# ASCII_08_FPGA_banks_1_2_3_4.net
KiCad netlist of a schematic drawn in Altium Designer
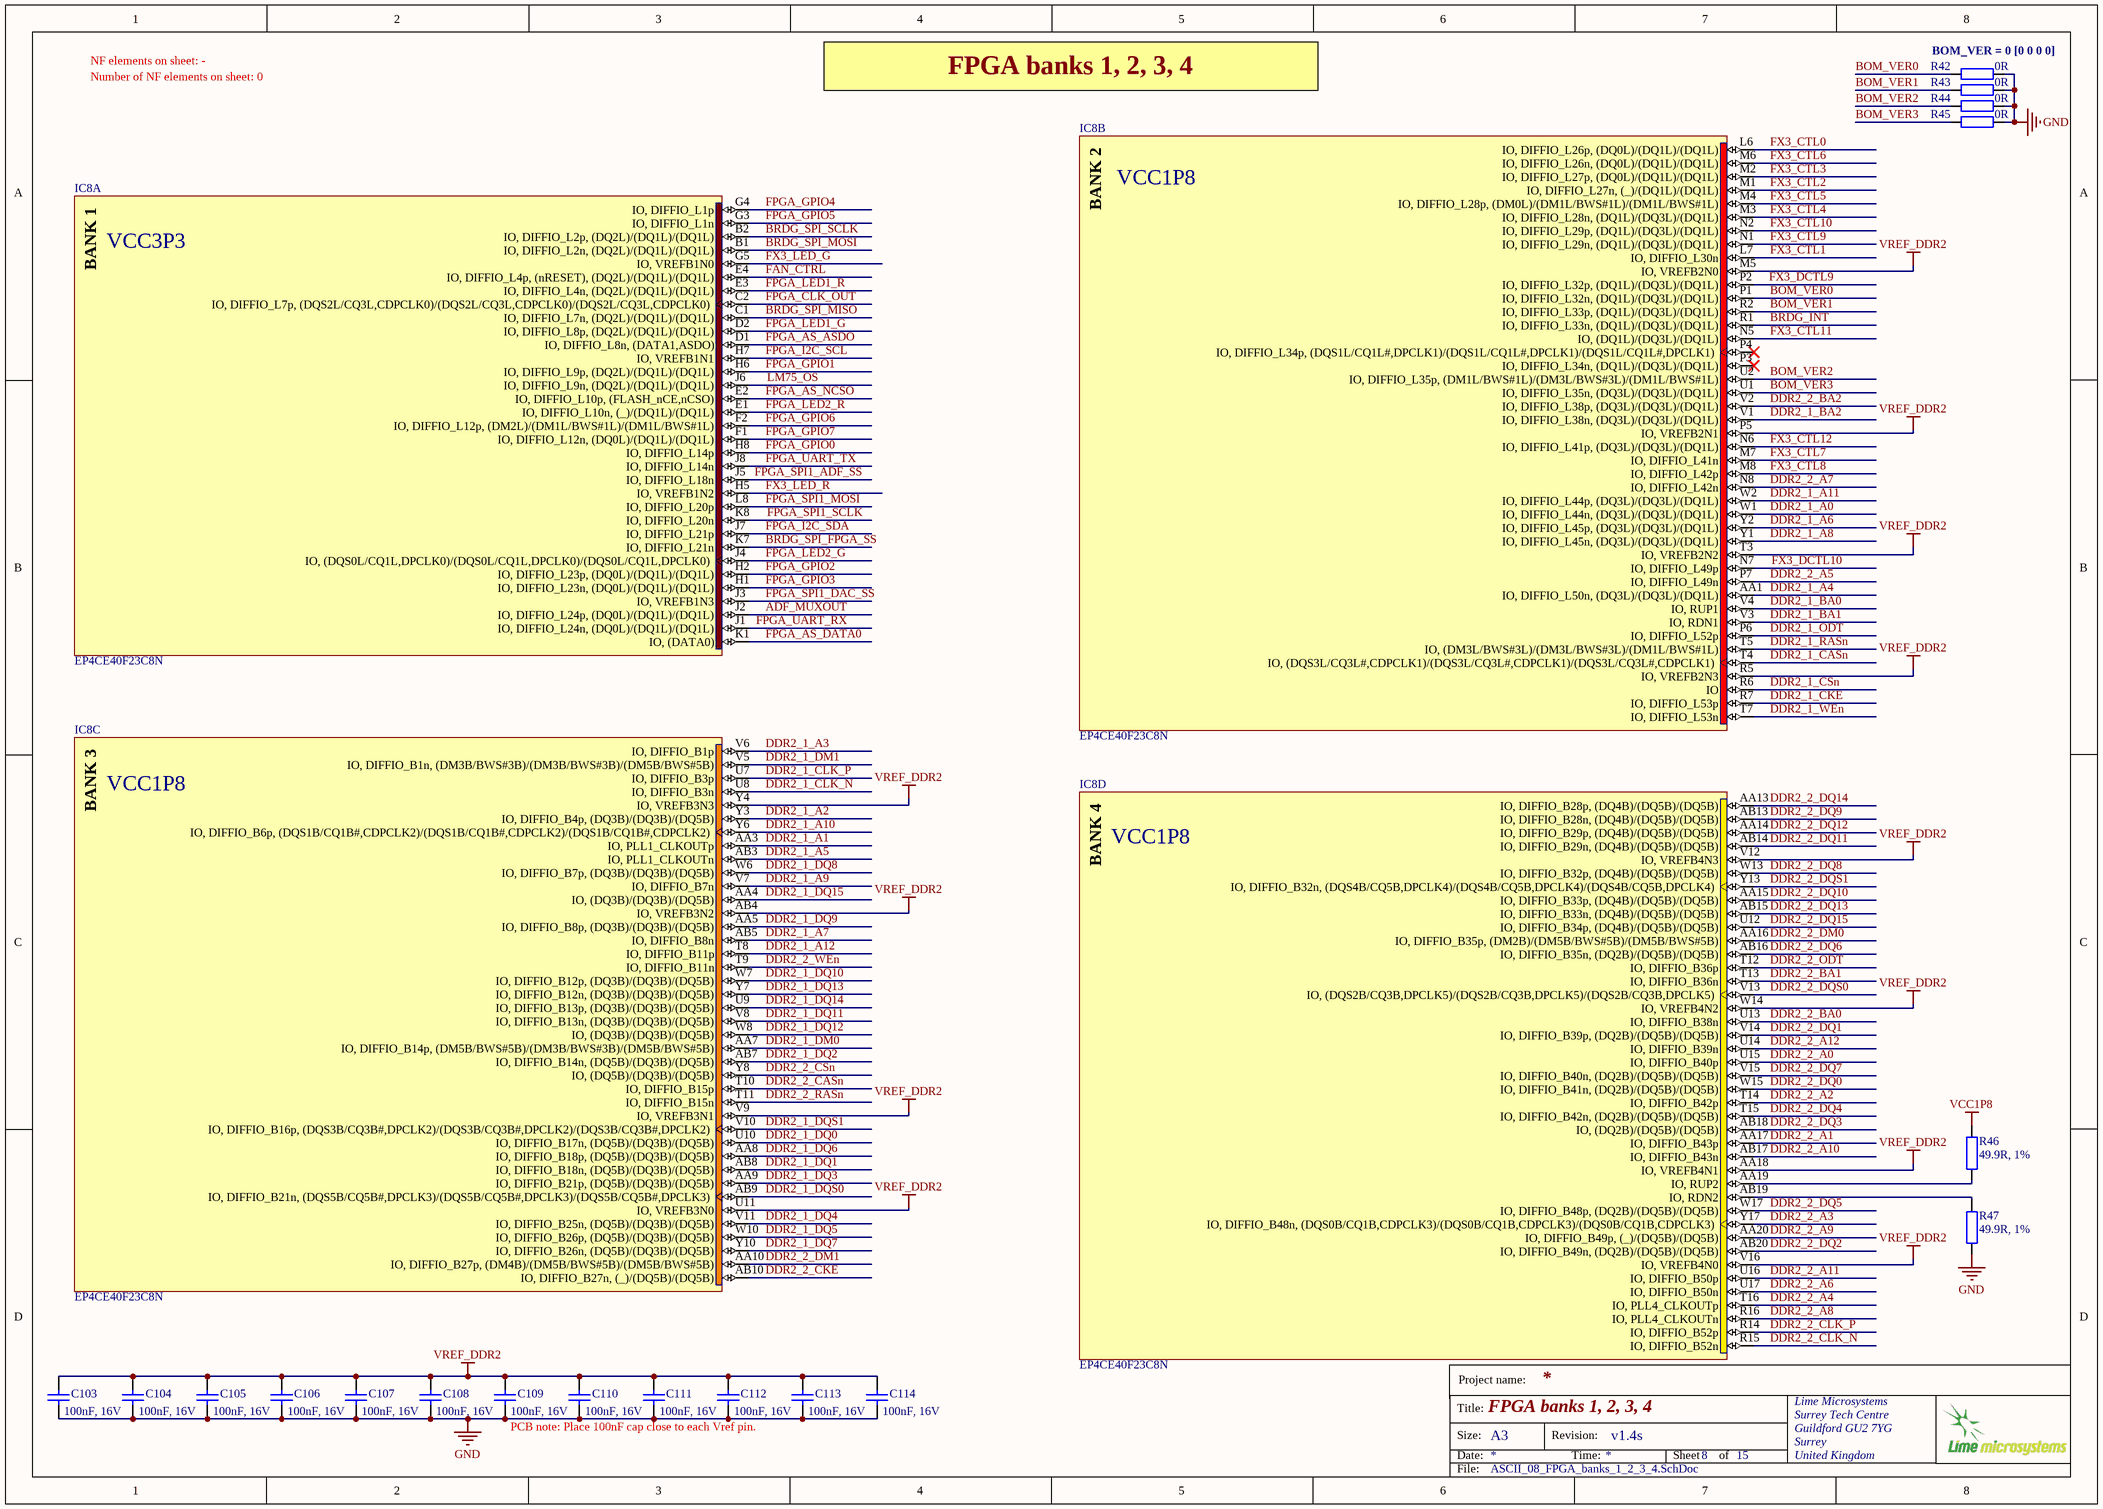
[diagram p0: ASCII_08_FPGA_banks_1_2_3_4.SchDoc]

(export (version "E")
  (design (tool "Eeschema 10.0.6"))
  (components
    (comp (ref "C103")
      (value "100nF, 16V")
      (footprint "CAP0402")
      (fields
        (field (name "TOLERANCE") "10 %")
        (field (name "MANUFACTURER") "Murata Electronics")
        (field (name "MANUFACTURER PART NUMBER") "GRM155R71C104KA88D")
      )
      (libsource (lib "LimeFPGAboard_schLib") (part "Cap_0603"))
    )
    (comp (ref "C104")
      (value "100nF, 16V")
      (footprint "CAP0402")
      (fields
        (field (name "TOLERANCE") "10 %")
        (field (name "MANUFACTURER") "Murata Electronics")
        (field (name "MANUFACTURER PART NUMBER") "GRM155R71C104KA88D")
      )
      (libsource (lib "LimeFPGAboard_schLib") (part "Cap_0603"))
    )
    (comp (ref "C105")
      (value "100nF, 16V")
      (footprint "CAP0402")
      (fields
        (field (name "TOLERANCE") "10 %")
        (field (name "MANUFACTURER") "Murata Electronics")
        (field (name "MANUFACTURER PART NUMBER") "GRM155R71C104KA88D")
      )
      (libsource (lib "LimeFPGAboard_schLib") (part "Cap_0603"))
    )
    (comp (ref "C106")
      (value "100nF, 16V")
      (footprint "CAP0402")
      (fields
        (field (name "TOLERANCE") "10 %")
        (field (name "MANUFACTURER") "Murata Electronics")
        (field (name "MANUFACTURER PART NUMBER") "GRM155R71C104KA88D")
      )
      (libsource (lib "LimeFPGAboard_schLib") (part "Cap_0603"))
    )
    (comp (ref "C107")
      (value "100nF, 16V")
      (footprint "CAP0402")
      (fields
        (field (name "TOLERANCE") "10 %")
        (field (name "MANUFACTURER") "Murata Electronics")
        (field (name "MANUFACTURER PART NUMBER") "GRM155R71C104KA88D")
      )
      (libsource (lib "LimeFPGAboard_schLib") (part "Cap_0603"))
    )
    (comp (ref "C108")
      (value "100nF, 16V")
      (footprint "CAP0402")
      (fields
        (field (name "TOLERANCE") "10 %")
        (field (name "MANUFACTURER") "Murata Electronics")
        (field (name "MANUFACTURER PART NUMBER") "GRM155R71C104KA88D")
      )
      (libsource (lib "LimeFPGAboard_schLib") (part "Cap_0603"))
    )
    (comp (ref "C109")
      (value "100nF, 16V")
      (footprint "CAP0402")
      (fields
        (field (name "TOLERANCE") "10 %")
        (field (name "MANUFACTURER") "Murata Electronics")
        (field (name "MANUFACTURER PART NUMBER") "GRM155R71C104KA88D")
      )
      (libsource (lib "LimeFPGAboard_schLib") (part "Cap_0603"))
    )
    (comp (ref "C110")
      (value "100nF, 16V")
      (footprint "CAP0402")
      (fields
        (field (name "TOLERANCE") "10 %")
        (field (name "MANUFACTURER") "Murata Electronics")
        (field (name "MANUFACTURER PART NUMBER") "GRM155R71C104KA88D")
      )
      (libsource (lib "LimeFPGAboard_schLib") (part "Cap_0603"))
    )
    (comp (ref "C111")
      (value "100nF, 16V")
      (footprint "CAP0402")
      (fields
        (field (name "TOLERANCE") "10 %")
        (field (name "MANUFACTURER") "Murata Electronics")
        (field (name "MANUFACTURER PART NUMBER") "GRM155R71C104KA88D")
      )
      (libsource (lib "LimeFPGAboard_schLib") (part "Cap_0603"))
    )
    (comp (ref "C112")
      (value "100nF, 16V")
      (footprint "CAP0402")
      (fields
        (field (name "TOLERANCE") "10 %")
        (field (name "MANUFACTURER") "Murata Electronics")
        (field (name "MANUFACTURER PART NUMBER") "GRM155R71C104KA88D")
      )
      (libsource (lib "LimeFPGAboard_schLib") (part "Cap_0603"))
    )
    (comp (ref "C113")
      (value "100nF, 16V")
      (footprint "CAP0402")
      (fields
        (field (name "TOLERANCE") "10 %")
        (field (name "MANUFACTURER") "Murata Electronics")
        (field (name "MANUFACTURER PART NUMBER") "GRM155R71C104KA88D")
      )
      (libsource (lib "LimeFPGAboard_schLib") (part "Cap_0603"))
    )
    (comp (ref "C114")
      (value "100nF, 16V")
      (footprint "CAP0402")
      (fields
        (field (name "TOLERANCE") "10 %")
        (field (name "MANUFACTURER") "Murata Electronics")
        (field (name "MANUFACTURER PART NUMBER") "GRM155R71C104KA88D")
      )
      (libsource (lib "LimeFPGAboard_schLib") (part "Cap_0603"))
    )
    (comp (ref "IC8")
      (value "EP4CE40F23C8N")
      (footprint "FBGA484_A-240")
      (description "IC FPGA 328 I/O 484FBGA")
      (fields (field (name "MANUFACTURER") "Altera"))
      (libsource (lib "LimeMicroAltiumLib_schLib") (part "EP4CE40F23C7N"))
    )
    (comp (ref "R42")
      (value "0R")
      (footprint "RES0402")
      (fields (field (name "MANUFACTURER") "Yageo"))
      (libsource (lib "LimeFPGAboard_schLib") (part "Res_0402"))
    )
    (comp (ref "R43")
      (value "0R")
      (footprint "RES0402")
      (fields (field (name "MANUFACTURER") "Yageo"))
      (libsource (lib "LimeFPGAboard_schLib") (part "Res_0402"))
    )
    (comp (ref "R44")
      (value "0R")
      (footprint "RES0402")
      (fields (field (name "MANUFACTURER") "Yageo"))
      (libsource (lib "LimeFPGAboard_schLib") (part "Res_0402"))
    )
    (comp (ref "R45")
      (value "0R")
      (footprint "RES0402")
      (fields (field (name "MANUFACTURER") "Yageo"))
      (libsource (lib "LimeFPGAboard_schLib") (part "Res_0402"))
    )
    (comp (ref "R46")
      (value "49.9R, 1%")
      (footprint "RES0402")
      (fields
        (field (name "TOLERANCE") "±1%")
        (field (name "MANUFACTURER") "Samsung Electro-Mechanics America, Inc.")
        (field (name "MANUFACTURER PART NUMBER") "RC1005F49R9CS")
      )
      (libsource (lib "LimeMicroAltiumLib_schLib") (part "Res_0402"))
    )
    (comp (ref "R47")
      (value "49.9R, 1%")
      (footprint "RES0402")
      (fields
        (field (name "TOLERANCE") "±1%")
        (field (name "MANUFACTURER") "Samsung Electro-Mechanics America, Inc.")
        (field (name "MANUFACTURER PART NUMBER") "RC1005F49R9CS")
      )
      (libsource (lib "LimeMicroAltiumLib_schLib") (part "Res_0402"))
    )
  )
  (nets
    (net (code "1") (name "/ADF_MUXOUT") (class "Default")
      (node (ref "IC8") (pin "J2") (pinfunction "IO,_DIFFIO_L24p,_(DQ0L)/(DQ1L)/(DQ1L)_J2") (pintype "bidirectional"))
    )
    (net (code "2") (name "/BOM_VER0") (class "Default")
      (node (ref "IC8") (pin "P1") (pinfunction "IO,_DIFFIO_L32n,_(DQ1L)/(DQ3L)/(DQ1L)_P1") (pintype "bidirectional"))
      (node (ref "R42") (pin "1") (pinfunction "1_1") (pintype "passive"))
    )
    (net (code "3") (name "/BOM_VER1") (class "Default")
      (node (ref "IC8") (pin "R2") (pinfunction "IO,_DIFFIO_L33p,_(DQ1L)/(DQ3L)/(DQ1L)_R2") (pintype "bidirectional"))
      (node (ref "R43") (pin "1") (pinfunction "1_1") (pintype "passive"))
    )
    (net (code "4") (name "/BOM_VER2") (class "Default")
      (node (ref "IC8") (pin "U2") (pinfunction "IO,_DIFFIO_L35p,_(DM1L/BWS#1L)/(DM3L/BWS#3L)/(DM1L/BWS#1L)_U2") (pintype "bidirectional"))
      (node (ref "R44") (pin "1") (pinfunction "1_1") (pintype "passive"))
    )
    (net (code "5") (name "/BOM_VER3") (class "Default")
      (node (ref "IC8") (pin "U1") (pinfunction "IO,_DIFFIO_L35n,_(DQ3L)/(DQ3L)/(DQ1L)_U1") (pintype "bidirectional"))
      (node (ref "R45") (pin "1") (pinfunction "1_1") (pintype "passive"))
    )
    (net (code "6") (name "/BRDG_INT") (class "Default")
      (node (ref "IC8") (pin "R1") (pinfunction "IO,_DIFFIO_L33n,_(DQ1L)/(DQ3L)/(DQ1L)_R1") (pintype "bidirectional"))
    )
    (net (code "7") (name "/BRDG_SPI_FPGA_SS") (class "Default")
      (node (ref "IC8") (pin "K7") (pinfunction "IO,_DIFFIO_L21n_K7") (pintype "bidirectional"))
    )
    (net (code "8") (name "/BRDG_SPI_MISO") (class "Default")
      (node (ref "IC8") (pin "C1") (pinfunction "IO,_DIFFIO_L7n,_(DQ2L)/(DQ1L)/(DQ1L)_C1") (pintype "bidirectional"))
    )
    (net (code "9") (name "/BRDG_SPI_MOSI") (class "Default")
      (node (ref "IC8") (pin "B1") (pinfunction "IO,_DIFFIO_L2n,_(DQ2L)/(DQ1L)/(DQ1L)_B1") (pintype "bidirectional"))
    )
    (net (code "10") (name "/BRDG_SPI_SCLK") (class "Default")
      (node (ref "IC8") (pin "B2") (pinfunction "IO,_DIFFIO_L2p,_(DQ2L)/(DQ1L)/(DQ1L)_B2") (pintype "bidirectional"))
    )
    (net (code "11") (name "/DDR2_1_A0") (class "Default")
      (node (ref "IC8") (pin "W1") (pinfunction "IO,_DIFFIO_L44n,_(DQ3L)/(DQ3L)/(DQ1L)_W1") (pintype "bidirectional"))
    )
    (net (code "12") (name "/DDR2_1_A1") (class "Default")
      (node (ref "IC8") (pin "AA3") (pinfunction "IO,_PLL1_CLKOUTp_AA3") (pintype "bidirectional"))
    )
    (net (code "13") (name "/DDR2_1_A2") (class "Default")
      (node (ref "IC8") (pin "Y3") (pinfunction "IO,_DIFFIO_B4p,_(DQ3B)/(DQ3B)/(DQ5B)_Y3") (pintype "bidirectional"))
    )
    (net (code "14") (name "/DDR2_1_A3") (class "Default")
      (node (ref "IC8") (pin "V6") (pinfunction "IO,_DIFFIO_B1p_V6") (pintype "bidirectional"))
    )
    (net (code "15") (name "/DDR2_1_A4") (class "Default")
      (node (ref "IC8") (pin "AA1") (pinfunction "IO,_DIFFIO_L50n,_(DQ3L)/(DQ3L)/(DQ1L)_AA1") (pintype "bidirectional"))
    )
    (net (code "16") (name "/DDR2_1_A5") (class "Default")
      (node (ref "IC8") (pin "AB3") (pinfunction "IO,_PLL1_CLKOUTn_AB3") (pintype "bidirectional"))
    )
    (net (code "17") (name "/DDR2_1_A6") (class "Default")
      (node (ref "IC8") (pin "Y2") (pinfunction "IO,_DIFFIO_L45p,_(DQ3L)/(DQ3L)/(DQ1L)_Y2") (pintype "bidirectional"))
    )
    (net (code "18") (name "/DDR2_1_A7") (class "Default")
      (node (ref "IC8") (pin "AB5") (pinfunction "IO,_DIFFIO_B8n_AB5") (pintype "bidirectional"))
    )
    (net (code "19") (name "/DDR2_1_A8") (class "Default")
      (node (ref "IC8") (pin "Y1") (pinfunction "IO,_DIFFIO_L45n,_(DQ3L)/(DQ3L)/(DQ1L)_Y1") (pintype "bidirectional"))
    )
    (net (code "20") (name "/DDR2_1_A9") (class "Default")
      (node (ref "IC8") (pin "V7") (pinfunction "IO,_DIFFIO_B7n_V7") (pintype "bidirectional"))
    )
    (net (code "21") (name "/DDR2_1_A10") (class "Default")
      (node (ref "IC8") (pin "Y6") (pinfunction "IO,_DIFFIO_B6p,_(DQS1B/CQ1B#,CDPCLK2)/(DQS1B/CQ1B#,CDPCLK2)/(DQS1B/CQ1B#,CDPCLK2)_Y6") (pintype "bidirectional"))
    )
    (net (code "22") (name "/DDR2_1_A11") (class "Default")
      (node (ref "IC8") (pin "W2") (pinfunction "IO,_DIFFIO_L44p,_(DQ3L)/(DQ3L)/(DQ1L)_W2") (pintype "bidirectional"))
    )
    (net (code "23") (name "/DDR2_1_A12") (class "Default")
      (node (ref "IC8") (pin "T8") (pinfunction "IO,_DIFFIO_B11p_T8") (pintype "bidirectional"))
    )
    (net (code "24") (name "/DDR2_1_BA0") (class "Default")
      (node (ref "IC8") (pin "V4") (pinfunction "IO,_RUP1_V4") (pintype "bidirectional"))
    )
    (net (code "25") (name "/DDR2_1_BA1") (class "Default")
      (node (ref "IC8") (pin "V3") (pinfunction "IO,_RDN1_V3") (pintype "bidirectional"))
    )
    (net (code "26") (name "/DDR2_1_BA2") (class "Default")
      (node (ref "IC8") (pin "V1") (pinfunction "IO,_DIFFIO_L38n,_(DQ3L)/(DQ3L)/(DQ1L)_V1") (pintype "bidirectional"))
    )
    (net (code "27") (name "/DDR2_1_CASn") (class "Default")
      (node (ref "IC8") (pin "T4") (pinfunction "IO,_(DQS3L/CQ3L#,CDPCLK1)/(DQS3L/CQ3L#,CDPCLK1)/(DQS3L/CQ3L#,CDPCLK1)_T4") (pintype "bidirectional"))
    )
    (net (code "28") (name "/DDR2_1_CKE") (class "Default")
      (node (ref "IC8") (pin "R7") (pinfunction "IO,_DIFFIO_L53p_R7") (pintype "bidirectional"))
    )
    (net (code "29") (name "/DDR2_1_CLK_N") (class "Default")
      (node (ref "IC8") (pin "U8") (pinfunction "IO,_DIFFIO_B3n_U8") (pintype "bidirectional"))
    )
    (net (code "30") (name "/DDR2_1_CLK_P") (class "Default")
      (node (ref "IC8") (pin "U7") (pinfunction "IO,_DIFFIO_B3p_U7") (pintype "bidirectional"))
    )
    (net (code "31") (name "/DDR2_1_CSn") (class "Default")
      (node (ref "IC8") (pin "R6") (pinfunction "IO_R6") (pintype "bidirectional"))
    )
    (net (code "32") (name "/DDR2_1_DM0") (class "Default")
      (node (ref "IC8") (pin "AA7") (pinfunction "IO,_DIFFIO_B14p,_(DM5B/BWS#5B)/(DM3B/BWS#3B)/(DM5B/BWS#5B)_AA7") (pintype "bidirectional"))
    )
    (net (code "33") (name "/DDR2_1_DM1") (class "Default")
      (node (ref "IC8") (pin "V5") (pinfunction "IO,_DIFFIO_B1n,_(DM3B/BWS#3B)/(DM3B/BWS#3B)/(DM5B/BWS#5B)_V5") (pintype "bidirectional"))
    )
    (net (code "34") (name "/DDR2_1_DQ0") (class "Default")
      (node (ref "IC8") (pin "U10") (pinfunction "IO,_DIFFIO_B17n,_(DQ5B)/(DQ3B)/(DQ5B)_U10") (pintype "bidirectional"))
    )
    (net (code "35") (name "/DDR2_1_DQ1") (class "Default")
      (node (ref "IC8") (pin "AB8") (pinfunction "IO,_DIFFIO_B18n,_(DQ5B)/(DQ3B)/(DQ5B)_AB8") (pintype "bidirectional"))
    )
    (net (code "36") (name "/DDR2_1_DQ2") (class "Default")
      (node (ref "IC8") (pin "AB7") (pinfunction "IO,_DIFFIO_B14n,_(DQ5B)/(DQ3B)/(DQ5B)_AB7") (pintype "bidirectional"))
    )
    (net (code "37") (name "/DDR2_1_DQ3") (class "Default")
      (node (ref "IC8") (pin "AA9") (pinfunction "IO,_DIFFIO_B21p,_(DQ5B)/(DQ3B)/(DQ5B)_AA9") (pintype "bidirectional"))
    )
    (net (code "38") (name "/DDR2_1_DQ4") (class "Default")
      (node (ref "IC8") (pin "V11") (pinfunction "IO,_DIFFIO_B25n,_(DQ5B)/(DQ3B)/(DQ5B)_V11") (pintype "bidirectional"))
    )
    (net (code "39") (name "/DDR2_1_DQ5") (class "Default")
      (node (ref "IC8") (pin "W10") (pinfunction "IO,_DIFFIO_B26p,_(DQ5B)/(DQ3B)/(DQ5B)_W10") (pintype "bidirectional"))
    )
    (net (code "40") (name "/DDR2_1_DQ6") (class "Default")
      (node (ref "IC8") (pin "AA8") (pinfunction "IO,_DIFFIO_B18p,_(DQ5B)/(DQ3B)/(DQ5B)_AA8") (pintype "bidirectional"))
    )
    (net (code "41") (name "/DDR2_1_DQ7") (class "Default")
      (node (ref "IC8") (pin "Y10") (pinfunction "IO,_DIFFIO_B26n,_(DQ5B)/(DQ3B)/(DQ5B)_Y10") (pintype "bidirectional"))
    )
    (net (code "42") (name "/DDR2_1_DQ8") (class "Default")
      (node (ref "IC8") (pin "W6") (pinfunction "IO,_DIFFIO_B7p,_(DQ3B)/(DQ3B)/(DQ5B)_W6") (pintype "bidirectional"))
    )
    (net (code "43") (name "/DDR2_1_DQ9") (class "Default")
      (node (ref "IC8") (pin "AA5") (pinfunction "IO,_DIFFIO_B8p,_(DQ3B)/(DQ3B)/(DQ5B)_AA5") (pintype "bidirectional"))
    )
    (net (code "44") (name "/DDR2_1_DQ10") (class "Default")
      (node (ref "IC8") (pin "W7") (pinfunction "IO,_DIFFIO_B12p,_(DQ3B)/(DQ3B)/(DQ5B)_W7") (pintype "bidirectional"))
    )
    (net (code "45") (name "/DDR2_1_DQ11") (class "Default")
      (node (ref "IC8") (pin "V8") (pinfunction "IO,_DIFFIO_B13n,_(DQ3B)/(DQ3B)/(DQ5B)_V8") (pintype "bidirectional"))
    )
    (net (code "46") (name "/DDR2_1_DQ12") (class "Default")
      (node (ref "IC8") (pin "W8") (pinfunction "IO,_(DQ3B)/(DQ3B)/(DQ5B)_W8") (pintype "bidirectional"))
    )
    (net (code "47") (name "/DDR2_1_DQ13") (class "Default")
      (node (ref "IC8") (pin "Y7") (pinfunction "IO,_DIFFIO_B12n,_(DQ3B)/(DQ3B)/(DQ5B)_Y7") (pintype "bidirectional"))
    )
    (net (code "48") (name "/DDR2_1_DQ14") (class "Default")
      (node (ref "IC8") (pin "U9") (pinfunction "IO,_DIFFIO_B13p,_(DQ3B)/(DQ3B)/(DQ5B)_U9") (pintype "bidirectional"))
    )
    (net (code "49") (name "/DDR2_1_DQ15") (class "Default")
      (node (ref "IC8") (pin "AA4") (pinfunction "IO,_(DQ3B)/(DQ3B)/(DQ5B)_AA4") (pintype "bidirectional"))
    )
    (net (code "50") (name "/DDR2_1_DQS0") (class "Default")
      (node (ref "IC8") (pin "AB9") (pinfunction "IO,_DIFFIO_B21n,_(DQS5B/CQ5B#,DPCLK3)/(DQS5B/CQ5B#,DPCLK3)/(DQS5B/CQ5B#,DPCLK3)_AB9") (pintype "bidirectional"))
    )
    (net (code "51") (name "/DDR2_1_DQS1") (class "Default")
      (node (ref "IC8") (pin "V10") (pinfunction "IO,_DIFFIO_B16p,_(DQS3B/CQ3B#,DPCLK2)/(DQS3B/CQ3B#,DPCLK2)/(DQS3B/CQ3B#,DPCLK2)_V10") (pintype "bidirectional"))
    )
    (net (code "52") (name "/DDR2_1_ODT") (class "Default")
      (node (ref "IC8") (pin "P6") (pinfunction "IO,_DIFFIO_L52p_P6") (pintype "bidirectional"))
    )
    (net (code "53") (name "/DDR2_1_RASn") (class "Default")
      (node (ref "IC8") (pin "T5") (pinfunction "IO,_(DM3L/BWS#3L)/(DM3L/BWS#3L)/(DM1L/BWS#1L)_T5") (pintype "bidirectional"))
    )
    (net (code "54") (name "/DDR2_1_WEn") (class "Default")
      (node (ref "IC8") (pin "T7") (pinfunction "IO,_DIFFIO_L53n_T7") (pintype "bidirectional"))
    )
    (net (code "55") (name "/DDR2_2_A0") (class "Default")
      (node (ref "IC8") (pin "U15") (pinfunction "IO,_DIFFIO_B40p_U15") (pintype "bidirectional"))
    )
    (net (code "56") (name "/DDR2_2_A1") (class "Default")
      (node (ref "IC8") (pin "AA17") (pinfunction "IO,_DIFFIO_B43p_AA17") (pintype "bidirectional"))
    )
    (net (code "57") (name "/DDR2_2_A2") (class "Default")
      (node (ref "IC8") (pin "T14") (pinfunction "IO,_DIFFIO_B42p_T14") (pintype "bidirectional"))
    )
    (net (code "58") (name "/DDR2_2_A3") (class "Default")
      (node (ref "IC8") (pin "Y17") (pinfunction "IO,_DIFFIO_B48n,_(DQS0B/CQ1B,CDPCLK3)/(DQS0B/CQ1B,CDPCLK3)/(DQS0B/CQ1B,CDPCLK3)_Y17") (pintype "bidirectional"))
    )
    (net (code "59") (name "/DDR2_2_A4") (class "Default")
      (node (ref "IC8") (pin "T16") (pinfunction "IO,_PLL4_CLKOUTp_T16") (pintype "bidirectional"))
    )
    (net (code "60") (name "/DDR2_2_A5") (class "Default")
      (node (ref "IC8") (pin "P7") (pinfunction "IO,_DIFFIO_L49n_P7") (pintype "bidirectional"))
    )
    (net (code "61") (name "/DDR2_2_A6") (class "Default")
      (node (ref "IC8") (pin "U17") (pinfunction "IO,_DIFFIO_B50n_U17") (pintype "bidirectional"))
    )
    (net (code "62") (name "/DDR2_2_A7") (class "Default")
      (node (ref "IC8") (pin "N8") (pinfunction "IO,_DIFFIO_L42n_N8") (pintype "bidirectional"))
    )
    (net (code "63") (name "/DDR2_2_A8") (class "Default")
      (node (ref "IC8") (pin "R16") (pinfunction "IO,_PLL4_CLKOUTn_R16") (pintype "bidirectional"))
    )
    (net (code "64") (name "/DDR2_2_A9") (class "Default")
      (node (ref "IC8") (pin "AA20") (pinfunction "IO,_DIFFIO_B49p,_(_)/(DQ5B)/(DQ5B)_AA20") (pintype "bidirectional"))
    )
    (net (code "65") (name "/DDR2_2_A10") (class "Default")
      (node (ref "IC8") (pin "AB17") (pinfunction "IO,_DIFFIO_B43n_AB17") (pintype "bidirectional"))
    )
    (net (code "66") (name "/DDR2_2_A11") (class "Default")
      (node (ref "IC8") (pin "U16") (pinfunction "IO,_DIFFIO_B50p_U16") (pintype "bidirectional"))
    )
    (net (code "67") (name "/DDR2_2_A12") (class "Default")
      (node (ref "IC8") (pin "U14") (pinfunction "IO,_DIFFIO_B39n_U14") (pintype "bidirectional"))
    )
    (net (code "68") (name "/DDR2_2_BA0") (class "Default")
      (node (ref "IC8") (pin "U13") (pinfunction "IO,_DIFFIO_B38n_U13") (pintype "bidirectional"))
    )
    (net (code "69") (name "/DDR2_2_BA1") (class "Default")
      (node (ref "IC8") (pin "T13") (pinfunction "IO,_DIFFIO_B36n_T13") (pintype "bidirectional"))
    )
    (net (code "70") (name "/DDR2_2_BA2") (class "Default")
      (node (ref "IC8") (pin "V2") (pinfunction "IO,_DIFFIO_L38p,_(DQ3L)/(DQ3L)/(DQ1L)_V2") (pintype "bidirectional"))
    )
    (net (code "71") (name "/DDR2_2_CASn") (class "Default")
      (node (ref "IC8") (pin "T10") (pinfunction "IO,_DIFFIO_B15p_T10") (pintype "bidirectional"))
    )
    (net (code "72") (name "/DDR2_2_CKE") (class "Default")
      (node (ref "IC8") (pin "AB10") (pinfunction "IO,_DIFFIO_B27n,_(_)/(DQ5B)/(DQ5B)_AB10") (pintype "bidirectional"))
    )
    (net (code "73") (name "/DDR2_2_CLK_N") (class "Default")
      (node (ref "IC8") (pin "R15") (pinfunction "IO,_DIFFIO_B52n_R15") (pintype "bidirectional"))
    )
    (net (code "74") (name "/DDR2_2_CLK_P") (class "Default")
      (node (ref "IC8") (pin "R14") (pinfunction "IO,_DIFFIO_B52p_R14") (pintype "bidirectional"))
    )
    (net (code "75") (name "/DDR2_2_CSn") (class "Default")
      (node (ref "IC8") (pin "Y8") (pinfunction "IO,_(DQ5B)/(DQ3B)/(DQ5B)_Y8") (pintype "bidirectional"))
    )
    (net (code "76") (name "/DDR2_2_DM0") (class "Default")
      (node (ref "IC8") (pin "AA16") (pinfunction "IO,_DIFFIO_B35p,_(DM2B)/(DM5B/BWS#5B)/(DM5B/BWS#5B)_AA16") (pintype "bidirectional"))
    )
    (net (code "77") (name "/DDR2_2_DM1") (class "Default")
      (node (ref "IC8") (pin "AA10") (pinfunction "IO,_DIFFIO_B27p,_(DM4B)/(DM5B/BWS#5B)/(DM5B/BWS#5B)_AA10") (pintype "bidirectional"))
    )
    (net (code "78") (name "/DDR2_2_DQ0") (class "Default")
      (node (ref "IC8") (pin "W15") (pinfunction "IO,_DIFFIO_B41n,_(DQ2B)/(DQ5B)/(DQ5B)_W15") (pintype "bidirectional"))
    )
    (net (code "79") (name "/DDR2_2_DQ1") (class "Default")
      (node (ref "IC8") (pin "V14") (pinfunction "IO,_DIFFIO_B39p,_(DQ2B)/(DQ5B)/(DQ5B)_V14") (pintype "bidirectional"))
    )
    (net (code "80") (name "/DDR2_2_DQ2") (class "Default")
      (node (ref "IC8") (pin "AB20") (pinfunction "IO,_DIFFIO_B49n,_(DQ2B)/(DQ5B)/(DQ5B)_AB20") (pintype "bidirectional"))
    )
    (net (code "81") (name "/DDR2_2_DQ3") (class "Default")
      (node (ref "IC8") (pin "AB18") (pinfunction "IO,_(DQ2B)/(DQ5B)/(DQ5B)_AB18") (pintype "bidirectional"))
    )
    (net (code "82") (name "/DDR2_2_DQ4") (class "Default")
      (node (ref "IC8") (pin "T15") (pinfunction "IO,_DIFFIO_B42n,_(DQ2B)/(DQ5B)/(DQ5B)_T15") (pintype "bidirectional"))
    )
    (net (code "83") (name "/DDR2_2_DQ5") (class "Default")
      (node (ref "IC8") (pin "W17") (pinfunction "IO,_DIFFIO_B48p,_(DQ2B)/(DQ5B)/(DQ5B)_W17") (pintype "bidirectional"))
    )
    (net (code "84") (name "/DDR2_2_DQ6") (class "Default")
      (node (ref "IC8") (pin "AB16") (pinfunction "IO,_DIFFIO_B35n,_(DQ2B)/(DQ5B)/(DQ5B)_AB16") (pintype "bidirectional"))
    )
    (net (code "85") (name "/DDR2_2_DQ7") (class "Default")
      (node (ref "IC8") (pin "V15") (pinfunction "IO,_DIFFIO_B40n,_(DQ2B)/(DQ5B)/(DQ5B)_V15") (pintype "bidirectional"))
    )
    (net (code "86") (name "/DDR2_2_DQ8") (class "Default")
      (node (ref "IC8") (pin "W13") (pinfunction "IO,_DIFFIO_B32p,_(DQ4B)/(DQ5B)/(DQ5B)_W13") (pintype "bidirectional"))
    )
    (net (code "87") (name "/DDR2_2_DQ9") (class "Default")
      (node (ref "IC8") (pin "AB13") (pinfunction "IO,_DIFFIO_B28n,_(DQ4B)/(DQ5B)/(DQ5B)_AB13") (pintype "bidirectional"))
    )
    (net (code "88") (name "/DDR2_2_DQ10") (class "Default")
      (node (ref "IC8") (pin "AA15") (pinfunction "IO,_DIFFIO_B33p,_(DQ4B)/(DQ5B)/(DQ5B)_AA15") (pintype "bidirectional"))
    )
    (net (code "89") (name "/DDR2_2_DQ11") (class "Default")
      (node (ref "IC8") (pin "AB14") (pinfunction "IO,_DIFFIO_B29n,_(DQ4B)/(DQ5B)/(DQ5B)_AB14") (pintype "bidirectional"))
    )
    (net (code "90") (name "/DDR2_2_DQ12") (class "Default")
      (node (ref "IC8") (pin "AA14") (pinfunction "IO,_DIFFIO_B29p,_(DQ4B)/(DQ5B)/(DQ5B)_AA14") (pintype "bidirectional"))
    )
    (net (code "91") (name "/DDR2_2_DQ13") (class "Default")
      (node (ref "IC8") (pin "AB15") (pinfunction "IO,_DIFFIO_B33n,_(DQ4B)/(DQ5B)/(DQ5B)_AB15") (pintype "bidirectional"))
    )
    (net (code "92") (name "/DDR2_2_DQ14") (class "Default")
      (node (ref "IC8") (pin "AA13") (pinfunction "IO,_DIFFIO_B28p,_(DQ4B)/(DQ5B)/(DQ5B)_AA13") (pintype "bidirectional"))
    )
    (net (code "93") (name "/DDR2_2_DQ15") (class "Default")
      (node (ref "IC8") (pin "U12") (pinfunction "IO,_DIFFIO_B34p,_(DQ4B)/(DQ5B)/(DQ5B)_U12") (pintype "bidirectional"))
    )
    (net (code "94") (name "/DDR2_2_DQS0") (class "Default")
      (node (ref "IC8") (pin "V13") (pinfunction "IO,_(DQS2B/CQ3B,DPCLK5)/(DQS2B/CQ3B,DPCLK5)/(DQS2B/CQ3B,DPCLK5)_V13") (pintype "bidirectional"))
    )
    (net (code "95") (name "/DDR2_2_DQS1") (class "Default")
      (node (ref "IC8") (pin "Y13") (pinfunction "IO,_DIFFIO_B32n,_(DQS4B/CQ5B,DPCLK4)/(DQS4B/CQ5B,DPCLK4)/(DQS4B/CQ5B,DPCLK4)_Y13") (pintype "bidirectional"))
    )
    (net (code "96") (name "/DDR2_2_ODT") (class "Default")
      (node (ref "IC8") (pin "T12") (pinfunction "IO,_DIFFIO_B36p_T12") (pintype "bidirectional"))
    )
    (net (code "97") (name "/DDR2_2_RASn") (class "Default")
      (node (ref "IC8") (pin "T11") (pinfunction "IO,_DIFFIO_B15n_T11") (pintype "bidirectional"))
    )
    (net (code "98") (name "/DDR2_2_WEn") (class "Default")
      (node (ref "IC8") (pin "T9") (pinfunction "IO,_DIFFIO_B11n_T9") (pintype "bidirectional"))
    )
    (net (code "99") (name "/FAN_CTRL") (class "Default")
      (node (ref "IC8") (pin "E4") (pinfunction "IO,_DIFFIO_L4p,_(nRESET),_(DQ2L)/(DQ1L)/(DQ1L)_E4") (pintype "bidirectional"))
    )
    (net (code "100") (name "/FPGA_AS_ASDO") (class "Default")
      (node (ref "IC8") (pin "D1") (pinfunction "IO,_DIFFIO_L8n,_(DATA1,ASDO)_D1") (pintype "bidirectional"))
    )
    (net (code "101") (name "/FPGA_AS_DATA0") (class "Default")
      (node (ref "IC8") (pin "K1") (pinfunction "IO,_(DATA0)_K1") (pintype "bidirectional"))
    )
    (net (code "102") (name "/FPGA_AS_NCSO") (class "Default")
      (node (ref "IC8") (pin "E2") (pinfunction "IO,_DIFFIO_L10p,_(FLASH_nCE,nCSO)_E2") (pintype "bidirectional"))
    )
    (net (code "103") (name "/FPGA_CLK_OUT") (class "Default")
      (node (ref "IC8") (pin "C2") (pinfunction "IO,_DIFFIO_L7p,_(DQS2L/CQ3L,CDPCLK0)/(DQS2L/CQ3L,CDPCLK0)/(DQS2L/CQ3L,CDPCLK0)_C2") (pintype "bidirectional"))
    )
    (net (code "104") (name "/FPGA_GPIO0") (class "Default")
      (node (ref "IC8") (pin "H8") (pinfunction "IO,_DIFFIO_L14p_H8") (pintype "bidirectional"))
    )
    (net (code "105") (name "/FPGA_GPIO1") (class "Default")
      (node (ref "IC8") (pin "H6") (pinfunction "IO,_DIFFIO_L9p,_(DQ2L)/(DQ1L)/(DQ1L)_H6") (pintype "bidirectional"))
    )
    (net (code "106") (name "/FPGA_GPIO2") (class "Default")
      (node (ref "IC8") (pin "H2") (pinfunction "IO,_DIFFIO_L23p,_(DQ0L)/(DQ1L)/(DQ1L)_H2") (pintype "bidirectional"))
    )
    (net (code "107") (name "/FPGA_GPIO3") (class "Default")
      (node (ref "IC8") (pin "H1") (pinfunction "IO,_DIFFIO_L23n,_(DQ0L)/(DQ1L)/(DQ1L)_H1") (pintype "bidirectional"))
    )
    (net (code "108") (name "/FPGA_GPIO4") (class "Default")
      (node (ref "IC8") (pin "G4") (pinfunction "IO,_DIFFIO_L1p_G4") (pintype "bidirectional"))
    )
    (net (code "109") (name "/FPGA_GPIO5") (class "Default")
      (node (ref "IC8") (pin "G3") (pinfunction "IO,_DIFFIO_L1n_G3") (pintype "bidirectional"))
    )
    (net (code "110") (name "/FPGA_GPIO6") (class "Default")
      (node (ref "IC8") (pin "F2") (pinfunction "IO,_DIFFIO_L12p,_(DM2L)/(DM1L/BWS#1L)/(DM1L/BWS#1L)_F2") (pintype "bidirectional"))
    )
    (net (code "111") (name "/FPGA_GPIO7") (class "Default")
      (node (ref "IC8") (pin "F1") (pinfunction "IO,_DIFFIO_L12n,_(DQ0L)/(DQ1L)/(DQ1L)_F1") (pintype "bidirectional"))
    )
    (net (code "112") (name "/FPGA_I2C_SCL") (class "Default")
      (node (ref "IC8") (pin "H7") (pinfunction "IO,_VREFB1N1_H7") (pintype "bidirectional"))
    )
    (net (code "113") (name "/FPGA_I2C_SDA") (class "Default")
      (node (ref "IC8") (pin "J7") (pinfunction "IO,_DIFFIO_L21p_J7") (pintype "bidirectional"))
    )
    (net (code "114") (name "/FPGA_LED1_G") (class "Default")
      (node (ref "IC8") (pin "D2") (pinfunction "IO,_DIFFIO_L8p,_(DQ2L)/(DQ1L)/(DQ1L)_D2") (pintype "bidirectional"))
    )
    (net (code "115") (name "/FPGA_LED1_R") (class "Default")
      (node (ref "IC8") (pin "E3") (pinfunction "IO,_DIFFIO_L4n,_(DQ2L)/(DQ1L)/(DQ1L)_E3") (pintype "bidirectional"))
    )
    (net (code "116") (name "/FPGA_LED2_G") (class "Default")
      (node (ref "IC8") (pin "J4") (pinfunction "IO,_(DQS0L/CQ1L,DPCLK0)/(DQS0L/CQ1L,DPCLK0)/(DQS0L/CQ1L,DPCLK0)_J4") (pintype "bidirectional"))
    )
    (net (code "117") (name "/FPGA_LED2_R") (class "Default")
      (node (ref "IC8") (pin "E1") (pinfunction "IO,_DIFFIO_L10n,_(_)/(DQ1L)/(DQ1L)_E1") (pintype "bidirectional"))
    )
    (net (code "118") (name "/FPGA_SPI1_ADF_SS") (class "Default")
      (node (ref "IC8") (pin "J5") (pinfunction "IO,_DIFFIO_L18n_J5") (pintype "bidirectional"))
    )
    (net (code "119") (name "/FPGA_SPI1_DAC_SS") (class "Default")
      (node (ref "IC8") (pin "J3") (pinfunction "IO,_VREFB1N3_J3") (pintype "bidirectional"))
    )
    (net (code "120") (name "/FPGA_SPI1_MOSI") (class "Default")
      (node (ref "IC8") (pin "L8") (pinfunction "IO,_DIFFIO_L20p_L8") (pintype "bidirectional"))
    )
    (net (code "121") (name "/FPGA_SPI1_SCLK") (class "Default")
      (node (ref "IC8") (pin "K8") (pinfunction "IO,_DIFFIO_L20n_K8") (pintype "bidirectional"))
    )
    (net (code "122") (name "/FPGA_UART_RX") (class "Default")
      (node (ref "IC8") (pin "J1") (pinfunction "IO,_DIFFIO_L24n,_(DQ0L)/(DQ1L)/(DQ1L)_J1") (pintype "bidirectional"))
    )
    (net (code "123") (name "/FPGA_UART_TX") (class "Default")
      (node (ref "IC8") (pin "J8") (pinfunction "IO,_DIFFIO_L14n_J8") (pintype "bidirectional"))
    )
    (net (code "124") (name "/FX3_CTL0") (class "Default")
      (node (ref "IC8") (pin "L6") (pinfunction "IO,_DIFFIO_L26p,_(DQ0L)/(DQ1L)/(DQ1L)_L6") (pintype "bidirectional"))
    )
    (net (code "125") (name "/FX3_CTL1") (class "Default")
      (node (ref "IC8") (pin "L7") (pinfunction "IO,_DIFFIO_L30n_L7") (pintype "bidirectional"))
    )
    (net (code "126") (name "/FX3_CTL2") (class "Default")
      (node (ref "IC8") (pin "M1") (pinfunction "IO,_DIFFIO_L27n,_(_)/(DQ1L)/(DQ1L)_M1") (pintype "bidirectional"))
    )
    (net (code "127") (name "/FX3_CTL3") (class "Default")
      (node (ref "IC8") (pin "M2") (pinfunction "IO,_DIFFIO_L27p,_(DQ0L)/(DQ1L)/(DQ1L)_M2") (pintype "bidirectional"))
    )
    (net (code "128") (name "/FX3_CTL4") (class "Default")
      (node (ref "IC8") (pin "M3") (pinfunction "IO,_DIFFIO_L28n,_(DQ1L)/(DQ3L)/(DQ1L)_M3") (pintype "bidirectional"))
    )
    (net (code "129") (name "/FX3_CTL5") (class "Default")
      (node (ref "IC8") (pin "M4") (pinfunction "IO,_DIFFIO_L28p,_(DM0L)/(DM1L/BWS#1L)/(DM1L/BWS#1L)_M4") (pintype "bidirectional"))
    )
    (net (code "130") (name "/FX3_CTL6") (class "Default")
      (node (ref "IC8") (pin "M6") (pinfunction "IO,_DIFFIO_L26n,_(DQ0L)/(DQ1L)/(DQ1L)_M6") (pintype "bidirectional"))
    )
    (net (code "131") (name "/FX3_CTL7") (class "Default")
      (node (ref "IC8") (pin "M7") (pinfunction "IO,_DIFFIO_L41n_M7") (pintype "bidirectional"))
    )
    (net (code "132") (name "/FX3_CTL8") (class "Default")
      (node (ref "IC8") (pin "M8") (pinfunction "IO,_DIFFIO_L42p_M8") (pintype "bidirectional"))
    )
    (net (code "133") (name "/FX3_CTL9") (class "Default")
      (node (ref "IC8") (pin "N1") (pinfunction "IO,_DIFFIO_L29n,_(DQ1L)/(DQ3L)/(DQ1L)_N1") (pintype "bidirectional"))
    )
    (net (code "134") (name "/FX3_CTL10") (class "Default")
      (node (ref "IC8") (pin "N2") (pinfunction "IO,_DIFFIO_L29p,_(DQ1L)/(DQ3L)/(DQ1L)_N2") (pintype "bidirectional"))
    )
    (net (code "135") (name "/FX3_CTL11") (class "Default")
      (node (ref "IC8") (pin "N5") (pinfunction "IO,_(DQ1L)/(DQ3L)/(DQ1L)_N5") (pintype "bidirectional"))
    )
    (net (code "136") (name "/FX3_CTL12") (class "Default")
      (node (ref "IC8") (pin "N6") (pinfunction "IO,_DIFFIO_L41p,_(DQ3L)/(DQ3L)/(DQ1L)_N6") (pintype "bidirectional"))
    )
    (net (code "137") (name "/FX3_DCTL9") (class "Default")
      (node (ref "IC8") (pin "P2") (pinfunction "IO,_DIFFIO_L32p,_(DQ1L)/(DQ3L)/(DQ1L)_P2") (pintype "bidirectional"))
    )
    (net (code "138") (name "/FX3_DCTL10") (class "Default")
      (node (ref "IC8") (pin "N7") (pinfunction "IO,_DIFFIO_L49p_N7") (pintype "bidirectional"))
    )
    (net (code "139") (name "/FX3_LED_G") (class "Default")
      (node (ref "IC8") (pin "G5") (pinfunction "IO,_VREFB1N0_G5") (pintype "bidirectional"))
    )
    (net (code "140") (name "/FX3_LED_R") (class "Default")
      (node (ref "IC8") (pin "H5") (pinfunction "IO,_VREFB1N2_H5") (pintype "bidirectional"))
    )
    (net (code "141") (name "/LM75_OS") (class "Default")
      (node (ref "IC8") (pin "J6") (pinfunction "IO,_DIFFIO_L9n,_(DQ2L)/(DQ1L)/(DQ1L)_J6") (pintype "bidirectional"))
    )
    (net (code "142") (name "GND") (class "Default")
      (node (ref "C103") (pin "2") (pinfunction "2_2") (pintype "passive"))
      (node (ref "C104") (pin "2") (pinfunction "2_2") (pintype "passive"))
      (node (ref "C105") (pin "2") (pinfunction "2_2") (pintype "passive"))
      (node (ref "C106") (pin "2") (pinfunction "2_2") (pintype "passive"))
      (node (ref "C107") (pin "2") (pinfunction "2_2") (pintype "passive"))
      (node (ref "C108") (pin "2") (pinfunction "2_2") (pintype "passive"))
      (node (ref "C109") (pin "2") (pinfunction "2_2") (pintype "passive"))
      (node (ref "C110") (pin "2") (pinfunction "2_2") (pintype "passive"))
      (node (ref "C111") (pin "2") (pinfunction "2_2") (pintype "passive"))
      (node (ref "C112") (pin "2") (pinfunction "2_2") (pintype "passive"))
      (node (ref "C113") (pin "2") (pinfunction "2_2") (pintype "passive"))
      (node (ref "C114") (pin "2") (pinfunction "2_2") (pintype "passive"))
      (node (ref "R42") (pin "2") (pinfunction "2_2") (pintype "passive"))
      (node (ref "R43") (pin "2") (pinfunction "2_2") (pintype "passive"))
      (node (ref "R44") (pin "2") (pinfunction "2_2") (pintype "passive"))
      (node (ref "R45") (pin "2") (pinfunction "2_2") (pintype "passive"))
      (node (ref "R47") (pin "1") (pinfunction "1_1") (pintype "passive"))
    )
    (net (code "143") (name "Net-(IC8D-IO,_RDN2)") (class "Default")
      (node (ref "IC8") (pin "AB19") (pinfunction "IO,_RDN2_AB19") (pintype "bidirectional"))
      (node (ref "R47") (pin "2") (pinfunction "2_2") (pintype "passive"))
    )
    (net (code "144") (name "Net-(IC8D-IO,_RUP2)") (class "Default")
      (node (ref "IC8") (pin "AA19") (pinfunction "IO,_RUP2_AA19") (pintype "bidirectional"))
      (node (ref "R46") (pin "1") (pinfunction "1_1") (pintype "passive"))
    )
    (net (code "145") (name "VCC1P8") (class "Default")
      (node (ref "R46") (pin "2") (pinfunction "2_2") (pintype "passive"))
    )
    (net (code "146") (name "VREF_DDR2") (class "Default")
      (node (ref "C103") (pin "1") (pinfunction "1_1") (pintype "passive"))
      (node (ref "C104") (pin "1") (pinfunction "1_1") (pintype "passive"))
      (node (ref "C105") (pin "1") (pinfunction "1_1") (pintype "passive"))
      (node (ref "C106") (pin "1") (pinfunction "1_1") (pintype "passive"))
      (node (ref "C107") (pin "1") (pinfunction "1_1") (pintype "passive"))
      (node (ref "C108") (pin "1") (pinfunction "1_1") (pintype "passive"))
      (node (ref "C109") (pin "1") (pinfunction "1_1") (pintype "passive"))
      (node (ref "C110") (pin "1") (pinfunction "1_1") (pintype "passive"))
      (node (ref "C111") (pin "1") (pinfunction "1_1") (pintype "passive"))
      (node (ref "C112") (pin "1") (pinfunction "1_1") (pintype "passive"))
      (node (ref "C113") (pin "1") (pinfunction "1_1") (pintype "passive"))
      (node (ref "C114") (pin "1") (pinfunction "1_1") (pintype "passive"))
      (node (ref "IC8") (pin "AA18") (pinfunction "IO,_VREFB4N1_AA18") (pintype "bidirectional"))
      (node (ref "IC8") (pin "AB4") (pinfunction "IO,_VREFB3N2_AB4") (pintype "bidirectional"))
      (node (ref "IC8") (pin "M5") (pinfunction "IO,_VREFB2N0_M5") (pintype "bidirectional"))
      (node (ref "IC8") (pin "P5") (pinfunction "IO,_VREFB2N1_P5") (pintype "bidirectional"))
      (node (ref "IC8") (pin "R5") (pinfunction "IO,_VREFB2N3_R5") (pintype "bidirectional"))
      (node (ref "IC8") (pin "T3") (pinfunction "IO,_VREFB2N2_T3") (pintype "bidirectional"))
      (node (ref "IC8") (pin "U11") (pinfunction "IO,_VREFB3N0_U11") (pintype "bidirectional"))
      (node (ref "IC8") (pin "V12") (pinfunction "IO,_VREFB4N3_V12") (pintype "bidirectional"))
      (node (ref "IC8") (pin "V16") (pinfunction "IO,_VREFB4N0_V16") (pintype "bidirectional"))
      (node (ref "IC8") (pin "V9") (pinfunction "IO,_VREFB3N1_V9") (pintype "bidirectional"))
      (node (ref "IC8") (pin "W14") (pinfunction "IO,_VREFB4N2_W14") (pintype "bidirectional"))
      (node (ref "IC8") (pin "Y4") (pinfunction "IO,_VREFB3N3_Y4") (pintype "bidirectional"))
    )
    (net (code "147") (name "unconnected-(IC8B-IO,_DIFFIO_L34n,_(DQ1L){slash}(DQ3L){slash}(DQ1L)-PadP3)") (class "Default")
      (node (ref "IC8") (pin "P3") (pinfunction "IO,_DIFFIO_L34n,_(DQ1L)/(DQ3L)/(DQ1L)_P3") (pintype "bidirectional+no_connect"))
    )
    (net (code "148") (name "unconnected-(IC8B-IO,_DIFFIO_L34p,_(DQS1L{slash}CQ1L#,DPCLK1){slash}(DQS1L{slash}CQ1L#,DPCLK1){slash}(DQS1L{slash}CQ1L#,DPCLK1)-PadP4)") (class "Default")
      (node (ref "IC8") (pin "P4") (pinfunction "IO,_DIFFIO_L34p,_(DQS1L/CQ1L#,DPCLK1)/(DQS1L/CQ1L#,DPCLK1)/(DQS1L/CQ1L#,DPCLK1)_P4") (pintype "bidirectional+no_connect"))
    )
  )
)
